# SelfTestWiring.net
KiCad netlist of a schematic drawn in EAGLE
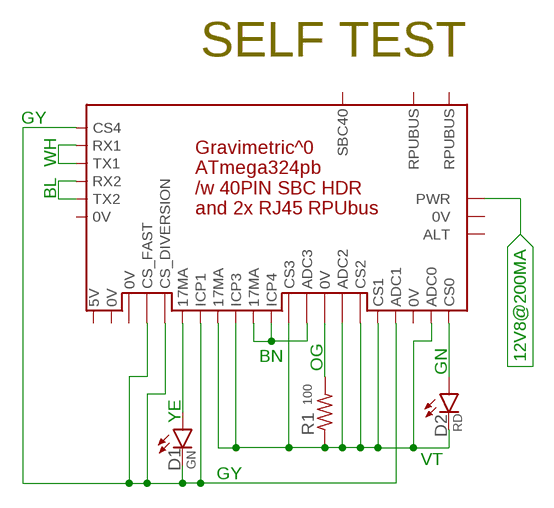
[diagram p0: schematic, sheet 1]

(export (version "E")
  (design (tool "Eeschema 10.0.6"))
  (components
    (comp (ref "D1")
      (value "GN")
      (footprint "eagle-import:LED5MM")
      (libsource (lib "eagle-import") (part "LED5MM"))
    )
    (comp (ref "D2")
      (value "RD")
      (footprint "eagle-import:LED5MM")
      (libsource (lib "eagle-import") (part "LED5MM"))
    )
    (comp (ref "R1")
      (value "100")
      (footprint "eagle-import:C0805(2012)")
      (libsource (lib "eagle-import") (part "R0805"))
    )
    (comp (ref "U$1")
      (value "GRAVIMETRIC")
      (footprint "eagle-import:WITH_RPU_NAMES")
      (libsource (lib "eagle-import") (part "GRAVIMETRIC"))
    )
  )
  (nets
    (net (code "1") (name "/BL") (class "Default")
      (node (ref "U$1") (pin "K2") (pinfunction "RX2_K2") (pintype "bidirectional"))
      (node (ref "U$1") (pin "K4") (pinfunction "TX2_K4") (pintype "bidirectional"))
    )
    (net (code "2") (name "/BN") (class "Default")
      (node (ref "U$1") (pin "17MA@ICP4") (pinfunction "17MA_17MA@ICP4") (pintype "bidirectional"))
      (node (ref "U$1") (pin "ADC3") (pinfunction "ADC3_ADC3") (pintype "bidirectional"))
      (node (ref "U$1") (pin "ICP4") (pinfunction "ICP4_ICP4") (pintype "bidirectional"))
    )
    (net (code "3") (name "/GN") (class "Default")
      (node (ref "D2") (pin "A") (pinfunction "A_A") (pintype "passive"))
      (node (ref "U$1") (pin "22MA@ADC1") (pinfunction "CS0_22MA@ADC1") (pintype "bidirectional"))
    )
    (net (code "4") (name "/GY") (class "Default")
      (node (ref "D1") (pin "K") (pinfunction "K_K") (pintype "passive"))
      (node (ref "U$1") (pin "22MA@ADC4") (pinfunction "CS4_22MA@ADC4") (pintype "bidirectional"))
      (node (ref "U$1") (pin "22MA@DIO2") (pinfunction "CS_DIVERSION_22MA@DIO2") (pintype "bidirectional"))
      (node (ref "U$1") (pin "22MA@DIO9") (pinfunction "CS_FAST_22MA@DIO9") (pintype "bidirectional"))
      (node (ref "U$1") (pin "ADC0") (pinfunction "ADC1_ADC0") (pintype "bidirectional"))
      (node (ref "U$1") (pin "ICP1") (pinfunction "ICP1_ICP1") (pintype "bidirectional"))
    )
    (net (code "5") (name "/OG") (class "Default")
      (node (ref "R1") (pin "2") (pinfunction "2_2") (pintype "passive"))
      (node (ref "U$1") (pin "0V@ADC2") (pinfunction "0V_0V@ADC2") (pintype "bidirectional"))
    )
    (net (code "6") (name "/VT") (class "Default")
      (node (ref "D2") (pin "K") (pinfunction "K_K") (pintype "passive"))
      (node (ref "R1") (pin "1") (pinfunction "1_1") (pintype "passive"))
      (node (ref "U$1") (pin "17MA@ICP3") (pinfunction "17MA_17MA@ICP3") (pintype "bidirectional"))
      (node (ref "U$1") (pin "22MA@ADC0") (pinfunction "CS1_22MA@ADC0") (pintype "bidirectional"))
      (node (ref "U$1") (pin "22MA@ADC2") (pinfunction "CS2_22MA@ADC2") (pintype "bidirectional"))
      (node (ref "U$1") (pin "22MA@ADC3") (pinfunction "CS3_22MA@ADC3") (pintype "bidirectional"))
      (node (ref "U$1") (pin "ADC1") (pinfunction "ADC0_ADC1") (pintype "bidirectional"))
      (node (ref "U$1") (pin "ADC2") (pinfunction "ADC2_ADC2") (pintype "bidirectional"))
      (node (ref "U$1") (pin "ICP3") (pinfunction "ICP3_ICP3") (pintype "bidirectional"))
    )
    (net (code "7") (name "/WH") (class "Default")
      (node (ref "U$1") (pin "K1") (pinfunction "RX1_K1") (pintype "bidirectional"))
      (node (ref "U$1") (pin "K3") (pinfunction "TX1_K3") (pintype "bidirectional"))
    )
    (net (code "8") (name "/YE") (class "Default")
      (node (ref "D1") (pin "A") (pinfunction "A_A") (pintype "passive"))
      (node (ref "U$1") (pin "17MA@ICP1") (pinfunction "17MA_17MA@ICP1") (pintype "bidirectional"))
    )
    (net (code "9") (name "12V8@200MA") (class "Default")
      (node (ref "U$1") (pin "PWR") (pinfunction "PWR_PWR") (pintype "bidirectional"))
    )
    (net (code "10") (name "unconnected-(U$1-0V-Pad0V@ADC1)") (class "Default")
      (node (ref "U$1") (pin "0V@ADC1") (pinfunction "0V_0V@ADC1") (pintype "bidirectional"))
    )
    (net (code "11") (name "unconnected-(U$1-0V-Pad0V@DIO2)") (class "Default")
      (node (ref "U$1") (pin "0V@DIO2") (pinfunction "0V_0V@DIO2") (pintype "bidirectional"))
    )
    (net (code "12") (name "unconnected-(U$1-0V-Pad0V@DIO9)") (class "Default")
      (node (ref "U$1") (pin "0V@DIO9") (pinfunction "0V_0V@DIO9") (pintype "bidirectional"))
    )
    (net (code "13") (name "unconnected-(U$1-0V-Pad0V@PWR)") (class "Default")
      (node (ref "U$1") (pin "0V@PWR") (pinfunction "0V_0V@PWR") (pintype "bidirectional"))
    )
    (net (code "14") (name "unconnected-(U$1-ALT-PadBAT)") (class "Default")
      (node (ref "U$1") (pin "BAT") (pinfunction "ALT_BAT") (pintype "bidirectional"))
    )
    (net (code "15") (name "unconnected-(U$1-Pad0V)") (class "Default")
      (node (ref "U$1") (pin "0V") (pinfunction "0V_0V") (pintype "bidirectional"))
    )
    (net (code "16") (name "unconnected-(U$1-Pad5V)") (class "Default")
      (node (ref "U$1") (pin "5V") (pinfunction "5V_5V") (pintype "bidirectional"))
    )
    (net (code "17") (name "unconnected-(U$1-RPUBUS-Pad+RX)") (class "Default")
      (node (ref "U$1") (pin "+RX") (pinfunction "RPUBUS_+RX") (pintype "bidirectional"))
    )
    (net (code "18") (name "unconnected-(U$1-RPUBUS-Pad+TX)") (class "Default")
      (node (ref "U$1") (pin "+TX") (pinfunction "RPUBUS_+TX") (pintype "bidirectional"))
    )
    (net (code "19") (name "unconnected-(U$1-SBC40-PadSPI)") (class "Default")
      (node (ref "U$1") (pin "SPI") (pinfunction "SBC40_SPI") (pintype "bidirectional"))
    )
  )
)
